# CD6871X3_7_3.net
KiCad netlist of a schematic drawn in EAGLE
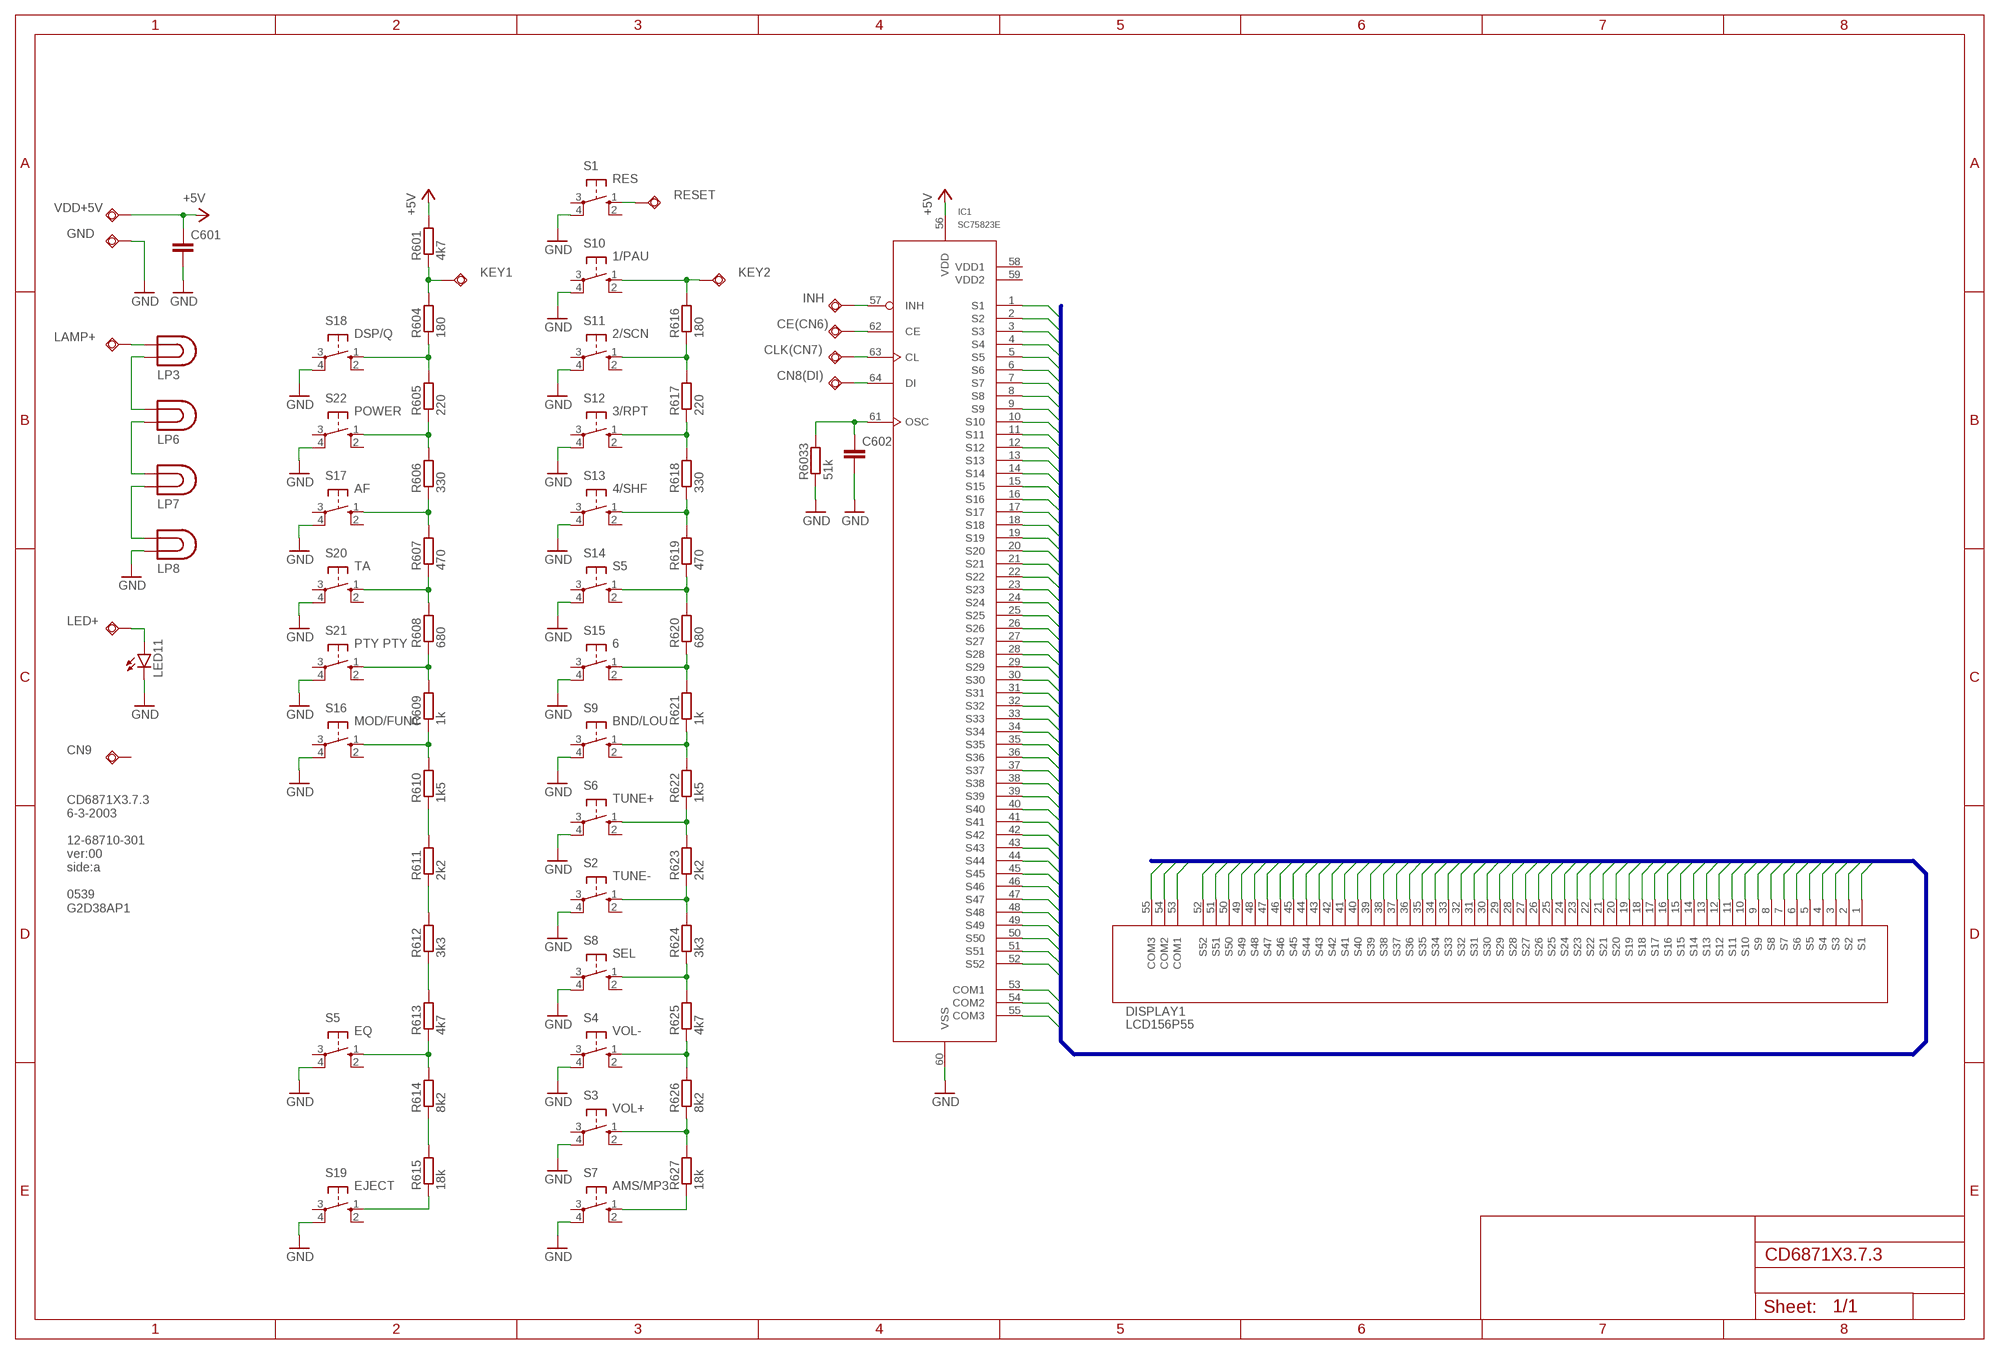
[diagram p0: schematic, sheet 1]

(export (version "E")
  (design (tool "Eeschema 10.0.6"))
  (components
    (comp (ref "C601")
      (value "C-EUC1310")
      (footprint "eagle-import:C1310")
      (libsource (lib "eagle-import") (part "C-EUC1310"))
    )
    (comp (ref "C602")
      (value "C-EUC1310")
      (footprint "eagle-import:C1310")
      (libsource (lib "eagle-import") (part "C-EUC1310"))
    )
    (comp (ref "CE(CN6)")
      (value "TPSQTP20SQ")
      (footprint "eagle-import:TP20SQ")
      (libsource (lib "eagle-import") (part "TPSQTP20SQ"))
    )
    (comp (ref "CLK(CN7)")
      (value "TPSQTP20SQ")
      (footprint "eagle-import:TP20SQ")
      (libsource (lib "eagle-import") (part "TPSQTP20SQ"))
    )
    (comp (ref "CN8(DI)")
      (value "TPSQTP20SQ")
      (footprint "eagle-import:TP20SQ")
      (libsource (lib "eagle-import") (part "TPSQTP20SQ"))
    )
    (comp (ref "CN9")
      (value "TPSQTP20SQ")
      (footprint "eagle-import:TP20SQ")
      (libsource (lib "eagle-import") (part "TPSQTP20SQ"))
    )
    (comp (ref "DISPLAY1")
      (value "LCD156P55")
      (footprint "eagle-import:LCD156P55")
      (libsource (lib "eagle-import") (part "LCD156P55"))
    )
    (comp (ref "GND")
      (value "TPSQTP20SQ")
      (footprint "eagle-import:TP20SQ")
      (libsource (lib "eagle-import") (part "TPSQTP20SQ"))
    )
    (comp (ref "IC1")
      (value "SC75823E")
      (footprint "eagle-import:QFP64_SOT393")
      (libsource (lib "eagle-import") (part "SC75823E"))
    )
    (comp (ref "INH")
      (value "TPSQTP20SQ")
      (footprint "eagle-import:TP20SQ")
      (libsource (lib "eagle-import") (part "TPSQTP20SQ"))
    )
    (comp (ref "KEY1")
      (value "TPSQTP20SQ")
      (footprint "eagle-import:TP20SQ")
      (libsource (lib "eagle-import") (part "TPSQTP20SQ"))
    )
    (comp (ref "KEY2")
      (value "TPSQTP20SQ")
      (footprint "eagle-import:TP20SQ")
      (libsource (lib "eagle-import") (part "TPSQTP20SQ"))
    )
    (comp (ref "LAMP+")
      (value "TPSQTP20SQ")
      (footprint "eagle-import:TP20SQ")
      (libsource (lib "eagle-import") (part "TPSQTP20SQ"))
    )
    (comp (ref "LED+")
      (value "TPSQTP20SQ")
      (footprint "eagle-import:TP20SQ")
      (libsource (lib "eagle-import") (part "TPSQTP20SQ"))
    )
    (comp (ref "LED11")
      (value "LED3MM")
      (footprint "eagle-import:LED3MM")
      (libsource (lib "eagle-import") (part "LED3MM"))
    )
    (comp (ref "LP3")
      (value "LAMP")
      (footprint "eagle-import:LDH-5R")
      (libsource (lib "eagle-import") (part "LAMP"))
    )
    (comp (ref "LP6")
      (value "LAMP")
      (footprint "eagle-import:LDH-5R")
      (libsource (lib "eagle-import") (part "LAMP"))
    )
    (comp (ref "LP7")
      (value "LAMP")
      (footprint "eagle-import:LDH-5R")
      (libsource (lib "eagle-import") (part "LAMP"))
    )
    (comp (ref "LP8")
      (value "LAMP")
      (footprint "eagle-import:LDH-5R")
      (libsource (lib "eagle-import") (part "LAMP"))
    )
    (comp (ref "R601")
      (value "4k7")
      (footprint "eagle-import:M1406")
      (libsource (lib "eagle-import") (part "R-EU_M1406"))
    )
    (comp (ref "R604")
      (value "180")
      (footprint "eagle-import:M1406")
      (libsource (lib "eagle-import") (part "R-EU_M1406"))
    )
    (comp (ref "R605")
      (value "220")
      (footprint "eagle-import:M1406")
      (libsource (lib "eagle-import") (part "R-EU_M1406"))
    )
    (comp (ref "R606")
      (value "330")
      (footprint "eagle-import:M1406")
      (libsource (lib "eagle-import") (part "R-EU_M1406"))
    )
    (comp (ref "R607")
      (value "470")
      (footprint "eagle-import:M1406")
      (libsource (lib "eagle-import") (part "R-EU_M1406"))
    )
    (comp (ref "R608")
      (value "680")
      (footprint "eagle-import:M1406")
      (libsource (lib "eagle-import") (part "R-EU_M1406"))
    )
    (comp (ref "R609")
      (value "1k")
      (footprint "eagle-import:M1406")
      (libsource (lib "eagle-import") (part "R-EU_M1406"))
    )
    (comp (ref "R610")
      (value "1k5")
      (footprint "eagle-import:M1406")
      (libsource (lib "eagle-import") (part "R-EU_M1406"))
    )
    (comp (ref "R611")
      (value "2k2")
      (footprint "eagle-import:M1406")
      (libsource (lib "eagle-import") (part "R-EU_M1406"))
    )
    (comp (ref "R612")
      (value "3k3")
      (footprint "eagle-import:M1406")
      (libsource (lib "eagle-import") (part "R-EU_M1406"))
    )
    (comp (ref "R613")
      (value "4k7")
      (footprint "eagle-import:M1406")
      (libsource (lib "eagle-import") (part "R-EU_M1406"))
    )
    (comp (ref "R614")
      (value "8k2")
      (footprint "eagle-import:M1406")
      (libsource (lib "eagle-import") (part "R-EU_M1406"))
    )
    (comp (ref "R615")
      (value "18k")
      (footprint "eagle-import:M1406")
      (libsource (lib "eagle-import") (part "R-EU_M1406"))
    )
    (comp (ref "R616")
      (value "180")
      (footprint "eagle-import:M1406")
      (libsource (lib "eagle-import") (part "R-EU_M1406"))
    )
    (comp (ref "R617")
      (value "220")
      (footprint "eagle-import:M1406")
      (libsource (lib "eagle-import") (part "R-EU_M1406"))
    )
    (comp (ref "R618")
      (value "330")
      (footprint "eagle-import:M1406")
      (libsource (lib "eagle-import") (part "R-EU_M1406"))
    )
    (comp (ref "R619")
      (value "470")
      (footprint "eagle-import:M1406")
      (libsource (lib "eagle-import") (part "R-EU_M1406"))
    )
    (comp (ref "R620")
      (value "680")
      (footprint "eagle-import:M1406")
      (libsource (lib "eagle-import") (part "R-EU_M1406"))
    )
    (comp (ref "R621")
      (value "1k")
      (footprint "eagle-import:M1406")
      (libsource (lib "eagle-import") (part "R-EU_M1406"))
    )
    (comp (ref "R622")
      (value "1k5")
      (footprint "eagle-import:M1406")
      (libsource (lib "eagle-import") (part "R-EU_M1406"))
    )
    (comp (ref "R623")
      (value "2k2")
      (footprint "eagle-import:M1406")
      (libsource (lib "eagle-import") (part "R-EU_M1406"))
    )
    (comp (ref "R624")
      (value "3k3")
      (footprint "eagle-import:M1406")
      (libsource (lib "eagle-import") (part "R-EU_M1406"))
    )
    (comp (ref "R625")
      (value "4k7")
      (footprint "eagle-import:M1406")
      (libsource (lib "eagle-import") (part "R-EU_M1406"))
    )
    (comp (ref "R626")
      (value "8k2")
      (footprint "eagle-import:M1406")
      (libsource (lib "eagle-import") (part "R-EU_M1406"))
    )
    (comp (ref "R627")
      (value "18k")
      (footprint "eagle-import:M1406")
      (libsource (lib "eagle-import") (part "R-EU_M1406"))
    )
    (comp (ref "R6033")
      (value "51k")
      (footprint "eagle-import:M1406")
      (libsource (lib "eagle-import") (part "R-EU_M1406"))
    )
    (comp (ref "RESET")
      (value "TPSQTP20SQ")
      (footprint "eagle-import:TP20SQ")
      (libsource (lib "eagle-import") (part "TPSQTP20SQ"))
    )
    (comp (ref "S1")
      (value "RES")
      (footprint "eagle-import:B3F-10XX")
      (fields (field (name "MPN") "B3F-1000"))
      (libsource (lib "eagle-import") (part "10-XX"))
    )
    (comp (ref "S2")
      (value "TUNE-")
      (footprint "eagle-import:B3F-10XX")
      (fields (field (name "MPN") "B3F-1000"))
      (libsource (lib "eagle-import") (part "10-XX"))
    )
    (comp (ref "S3")
      (value "VOL+")
      (footprint "eagle-import:B3F-10XX")
      (fields (field (name "MPN") "B3F-1000"))
      (libsource (lib "eagle-import") (part "10-XX"))
    )
    (comp (ref "S4")
      (value "VOL-")
      (footprint "eagle-import:B3F-10XX")
      (fields (field (name "MPN") "B3F-1000"))
      (libsource (lib "eagle-import") (part "10-XX"))
    )
    (comp (ref "S5")
      (value "EQ")
      (footprint "eagle-import:B3F-10XX")
      (fields (field (name "MPN") "B3F-1000"))
      (libsource (lib "eagle-import") (part "10-XX"))
    )
    (comp (ref "S6")
      (value "TUNE+")
      (footprint "eagle-import:B3F-10XX")
      (fields (field (name "MPN") "B3F-1000"))
      (libsource (lib "eagle-import") (part "10-XX"))
    )
    (comp (ref "S7")
      (value "AMS/MP3")
      (footprint "eagle-import:B3F-10XX")
      (fields (field (name "MPN") "B3F-1000"))
      (libsource (lib "eagle-import") (part "10-XX"))
    )
    (comp (ref "S8")
      (value "SEL")
      (footprint "eagle-import:B3F-10XX")
      (fields (field (name "MPN") "B3F-1000"))
      (libsource (lib "eagle-import") (part "10-XX"))
    )
    (comp (ref "S9")
      (value "BND/LOU")
      (footprint "eagle-import:B3F-10XX")
      (fields (field (name "MPN") "B3F-1000"))
      (libsource (lib "eagle-import") (part "10-XX"))
    )
    (comp (ref "S10")
      (value "1/PAU")
      (footprint "eagle-import:B3F-10XX")
      (fields (field (name "MPN") "B3F-1000"))
      (libsource (lib "eagle-import") (part "10-XX"))
    )
    (comp (ref "S11")
      (value "2/SCN")
      (footprint "eagle-import:B3F-10XX")
      (fields (field (name "MPN") "B3F-1000"))
      (libsource (lib "eagle-import") (part "10-XX"))
    )
    (comp (ref "S12")
      (value "3/RPT")
      (footprint "eagle-import:B3F-10XX")
      (fields (field (name "MPN") "B3F-1000"))
      (libsource (lib "eagle-import") (part "10-XX"))
    )
    (comp (ref "S13")
      (value "4/SHF")
      (footprint "eagle-import:B3F-10XX")
      (fields (field (name "MPN") "B3F-1000"))
      (libsource (lib "eagle-import") (part "10-XX"))
    )
    (comp (ref "S14")
      (value "S5")
      (footprint "eagle-import:B3F-10XX")
      (fields (field (name "MPN") "B3F-1000"))
      (libsource (lib "eagle-import") (part "10-XX"))
    )
    (comp (ref "S15")
      (value "6")
      (footprint "eagle-import:B3F-10XX")
      (fields (field (name "MPN") "B3F-1000"))
      (libsource (lib "eagle-import") (part "10-XX"))
    )
    (comp (ref "S16")
      (value "MOD/FUNC")
      (footprint "eagle-import:B3F-10XX")
      (fields (field (name "MPN") "B3F-1000"))
      (libsource (lib "eagle-import") (part "10-XX"))
    )
    (comp (ref "S17")
      (value "AF")
      (footprint "eagle-import:B3F-10XX")
      (fields (field (name "MPN") "B3F-1000"))
      (libsource (lib "eagle-import") (part "10-XX"))
    )
    (comp (ref "S18")
      (value "DSP/Q")
      (footprint "eagle-import:B3F-10XX")
      (fields (field (name "MPN") "B3F-1000"))
      (libsource (lib "eagle-import") (part "10-XX"))
    )
    (comp (ref "S19")
      (value "EJECT")
      (footprint "eagle-import:B3F-10XX")
      (fields (field (name "MPN") "B3F-1000"))
      (libsource (lib "eagle-import") (part "10-XX"))
    )
    (comp (ref "S20")
      (value "TA")
      (footprint "eagle-import:B3F-10XX")
      (fields (field (name "MPN") "B3F-1000"))
      (libsource (lib "eagle-import") (part "10-XX"))
    )
    (comp (ref "S21")
      (value "PTY PTY")
      (footprint "eagle-import:B3F-10XX")
      (fields (field (name "MPN") "B3F-1000"))
      (libsource (lib "eagle-import") (part "10-XX"))
    )
    (comp (ref "S22")
      (value "POWER")
      (footprint "eagle-import:B3F-10XX")
      (fields (field (name "MPN") "B3F-1000"))
      (libsource (lib "eagle-import") (part "10-XX"))
    )
    (comp (ref "VDD+5V")
      (value "TPSQTP20SQ")
      (footprint "eagle-import:TP20SQ")
      (libsource (lib "eagle-import") (part "TPSQTP20SQ"))
    )
  )
  (nets
    (net (code "1") (name "+5V") (class "Default")
      (node (ref "C601") (pin "1") (pinfunction "1_1") (pintype "passive"))
      (node (ref "IC1") (pin "56") (pinfunction "VDD_56") (pintype "power_in"))
      (node (ref "R601") (pin "2") (pinfunction "2_2") (pintype "passive"))
      (node (ref "VDD+5V") (pin "TP") (pinfunction "TP_TP") (pintype "input"))
    )
    (net (code "2") (name "/B$1") (class "Default")
      (node (ref "DISPLAY1") (pin "1") (pinfunction "S1_1") (pintype "input"))
      (node (ref "IC1") (pin "1") (pinfunction "S1_1") (pintype "output"))
    )
    (net (code "3") (name "/B$2") (class "Default")
      (node (ref "DISPLAY1") (pin "2") (pinfunction "S2_2") (pintype "input"))
      (node (ref "IC1") (pin "2") (pinfunction "S2_2") (pintype "output"))
    )
    (net (code "4") (name "/B$3") (class "Default")
      (node (ref "DISPLAY1") (pin "3") (pinfunction "S3_3") (pintype "input"))
      (node (ref "IC1") (pin "3") (pinfunction "S3_3") (pintype "output"))
    )
    (net (code "5") (name "/B$4") (class "Default")
      (node (ref "DISPLAY1") (pin "4") (pinfunction "S4_4") (pintype "input"))
      (node (ref "IC1") (pin "4") (pinfunction "S4_4") (pintype "output"))
    )
    (net (code "6") (name "/B$5") (class "Default")
      (node (ref "DISPLAY1") (pin "5") (pinfunction "S5_5") (pintype "input"))
      (node (ref "IC1") (pin "5") (pinfunction "S5_5") (pintype "output"))
    )
    (net (code "7") (name "/B$6") (class "Default")
      (node (ref "DISPLAY1") (pin "6") (pinfunction "S6_6") (pintype "input"))
      (node (ref "IC1") (pin "6") (pinfunction "S6_6") (pintype "output"))
    )
    (net (code "8") (name "/B$7") (class "Default")
      (node (ref "DISPLAY1") (pin "7") (pinfunction "S7_7") (pintype "input"))
      (node (ref "IC1") (pin "7") (pinfunction "S7_7") (pintype "output"))
    )
    (net (code "9") (name "/B$8") (class "Default")
      (node (ref "DISPLAY1") (pin "8") (pinfunction "S8_8") (pintype "input"))
      (node (ref "IC1") (pin "8") (pinfunction "S8_8") (pintype "output"))
    )
    (net (code "10") (name "/B$9") (class "Default")
      (node (ref "DISPLAY1") (pin "9") (pinfunction "S9_9") (pintype "input"))
      (node (ref "IC1") (pin "9") (pinfunction "S9_9") (pintype "output"))
    )
    (net (code "11") (name "/B$10") (class "Default")
      (node (ref "DISPLAY1") (pin "10") (pinfunction "S10_10") (pintype "input"))
      (node (ref "IC1") (pin "10") (pinfunction "S10_10") (pintype "output"))
    )
    (net (code "12") (name "/B$11") (class "Default")
      (node (ref "DISPLAY1") (pin "11") (pinfunction "S11_11") (pintype "input"))
      (node (ref "IC1") (pin "11") (pinfunction "S11_11") (pintype "output"))
    )
    (net (code "13") (name "/B$12") (class "Default")
      (node (ref "DISPLAY1") (pin "12") (pinfunction "S12_12") (pintype "input"))
      (node (ref "IC1") (pin "12") (pinfunction "S12_12") (pintype "output"))
    )
    (net (code "14") (name "/B$13") (class "Default")
      (node (ref "DISPLAY1") (pin "13") (pinfunction "S13_13") (pintype "input"))
      (node (ref "IC1") (pin "13") (pinfunction "S13_13") (pintype "output"))
    )
    (net (code "15") (name "/B$14") (class "Default")
      (node (ref "DISPLAY1") (pin "14") (pinfunction "S14_14") (pintype "input"))
      (node (ref "IC1") (pin "14") (pinfunction "S14_14") (pintype "output"))
    )
    (net (code "16") (name "/B$15") (class "Default")
      (node (ref "DISPLAY1") (pin "15") (pinfunction "S15_15") (pintype "input"))
      (node (ref "IC1") (pin "15") (pinfunction "S15_15") (pintype "output"))
    )
    (net (code "17") (name "/B$16") (class "Default")
      (node (ref "DISPLAY1") (pin "16") (pinfunction "S16_16") (pintype "input"))
      (node (ref "IC1") (pin "16") (pinfunction "S16_16") (pintype "output"))
    )
    (net (code "18") (name "/B$17") (class "Default")
      (node (ref "DISPLAY1") (pin "17") (pinfunction "S17_17") (pintype "input"))
      (node (ref "IC1") (pin "17") (pinfunction "S17_17") (pintype "output"))
    )
    (net (code "19") (name "/B$18") (class "Default")
      (node (ref "DISPLAY1") (pin "18") (pinfunction "S18_18") (pintype "input"))
      (node (ref "IC1") (pin "18") (pinfunction "S18_18") (pintype "output"))
    )
    (net (code "20") (name "/B$19") (class "Default")
      (node (ref "DISPLAY1") (pin "19") (pinfunction "S19_19") (pintype "input"))
      (node (ref "IC1") (pin "19") (pinfunction "S19_19") (pintype "output"))
    )
    (net (code "21") (name "/B$20") (class "Default")
      (node (ref "DISPLAY1") (pin "20") (pinfunction "S20_20") (pintype "input"))
      (node (ref "IC1") (pin "20") (pinfunction "S20_20") (pintype "output"))
    )
    (net (code "22") (name "/B$21") (class "Default")
      (node (ref "DISPLAY1") (pin "21") (pinfunction "S21_21") (pintype "input"))
      (node (ref "IC1") (pin "21") (pinfunction "S21_21") (pintype "output"))
    )
    (net (code "23") (name "/B$22") (class "Default")
      (node (ref "DISPLAY1") (pin "22") (pinfunction "S22_22") (pintype "input"))
      (node (ref "IC1") (pin "22") (pinfunction "S22_22") (pintype "output"))
    )
    (net (code "24") (name "/B$23") (class "Default")
      (node (ref "DISPLAY1") (pin "23") (pinfunction "S23_23") (pintype "input"))
      (node (ref "IC1") (pin "23") (pinfunction "S23_23") (pintype "output"))
    )
    (net (code "25") (name "/B$24") (class "Default")
      (node (ref "DISPLAY1") (pin "24") (pinfunction "S24_24") (pintype "input"))
      (node (ref "IC1") (pin "24") (pinfunction "S24_24") (pintype "output"))
    )
    (net (code "26") (name "/B$25") (class "Default")
      (node (ref "DISPLAY1") (pin "25") (pinfunction "S25_25") (pintype "input"))
      (node (ref "IC1") (pin "25") (pinfunction "S25_25") (pintype "output"))
    )
    (net (code "27") (name "/B$26") (class "Default")
      (node (ref "DISPLAY1") (pin "26") (pinfunction "S26_26") (pintype "input"))
      (node (ref "IC1") (pin "26") (pinfunction "S26_26") (pintype "output"))
    )
    (net (code "28") (name "/B$27") (class "Default")
      (node (ref "DISPLAY1") (pin "27") (pinfunction "S27_27") (pintype "input"))
      (node (ref "IC1") (pin "27") (pinfunction "S27_27") (pintype "output"))
    )
    (net (code "29") (name "/B$28") (class "Default")
      (node (ref "DISPLAY1") (pin "28") (pinfunction "S28_28") (pintype "input"))
      (node (ref "IC1") (pin "28") (pinfunction "S28_28") (pintype "output"))
    )
    (net (code "30") (name "/B$29") (class "Default")
      (node (ref "DISPLAY1") (pin "29") (pinfunction "S29_29") (pintype "input"))
      (node (ref "IC1") (pin "29") (pinfunction "S29_29") (pintype "output"))
    )
    (net (code "31") (name "/B$30") (class "Default")
      (node (ref "DISPLAY1") (pin "30") (pinfunction "S30_30") (pintype "input"))
      (node (ref "IC1") (pin "30") (pinfunction "S30_30") (pintype "output"))
    )
    (net (code "32") (name "/B$31") (class "Default")
      (node (ref "DISPLAY1") (pin "31") (pinfunction "S31_31") (pintype "input"))
      (node (ref "IC1") (pin "31") (pinfunction "S31_31") (pintype "output"))
    )
    (net (code "33") (name "/B$32") (class "Default")
      (node (ref "DISPLAY1") (pin "32") (pinfunction "S32_32") (pintype "input"))
      (node (ref "IC1") (pin "32") (pinfunction "S32_32") (pintype "output"))
    )
    (net (code "34") (name "/B$33") (class "Default")
      (node (ref "DISPLAY1") (pin "33") (pinfunction "S33_33") (pintype "input"))
      (node (ref "IC1") (pin "33") (pinfunction "S33_33") (pintype "output"))
    )
    (net (code "35") (name "/B$34") (class "Default")
      (node (ref "DISPLAY1") (pin "34") (pinfunction "S34_34") (pintype "input"))
      (node (ref "IC1") (pin "34") (pinfunction "S34_34") (pintype "output"))
    )
    (net (code "36") (name "/B$35") (class "Default")
      (node (ref "DISPLAY1") (pin "35") (pinfunction "S35_35") (pintype "input"))
      (node (ref "IC1") (pin "35") (pinfunction "S35_35") (pintype "output"))
    )
    (net (code "37") (name "/B$36") (class "Default")
      (node (ref "DISPLAY1") (pin "36") (pinfunction "S36_36") (pintype "input"))
      (node (ref "IC1") (pin "36") (pinfunction "S36_36") (pintype "output"))
    )
    (net (code "38") (name "/B$37") (class "Default")
      (node (ref "DISPLAY1") (pin "37") (pinfunction "S37_37") (pintype "input"))
      (node (ref "IC1") (pin "37") (pinfunction "S37_37") (pintype "output"))
    )
    (net (code "39") (name "/B$38") (class "Default")
      (node (ref "DISPLAY1") (pin "38") (pinfunction "S38_38") (pintype "input"))
      (node (ref "IC1") (pin "38") (pinfunction "S38_38") (pintype "output"))
    )
    (net (code "40") (name "/B$39") (class "Default")
      (node (ref "DISPLAY1") (pin "39") (pinfunction "S39_39") (pintype "input"))
      (node (ref "IC1") (pin "39") (pinfunction "S39_39") (pintype "output"))
    )
    (net (code "41") (name "/B$40") (class "Default")
      (node (ref "DISPLAY1") (pin "40") (pinfunction "S40_40") (pintype "input"))
      (node (ref "IC1") (pin "40") (pinfunction "S40_40") (pintype "output"))
    )
    (net (code "42") (name "/B$41") (class "Default")
      (node (ref "DISPLAY1") (pin "41") (pinfunction "S41_41") (pintype "input"))
      (node (ref "IC1") (pin "41") (pinfunction "S41_41") (pintype "output"))
    )
    (net (code "43") (name "/B$42") (class "Default")
      (node (ref "DISPLAY1") (pin "42") (pinfunction "S42_42") (pintype "input"))
      (node (ref "IC1") (pin "42") (pinfunction "S42_42") (pintype "output"))
    )
    (net (code "44") (name "/B$43") (class "Default")
      (node (ref "DISPLAY1") (pin "43") (pinfunction "S43_43") (pintype "input"))
      (node (ref "IC1") (pin "43") (pinfunction "S43_43") (pintype "output"))
    )
    (net (code "45") (name "/B$44") (class "Default")
      (node (ref "DISPLAY1") (pin "44") (pinfunction "S44_44") (pintype "input"))
      (node (ref "IC1") (pin "44") (pinfunction "S44_44") (pintype "output"))
    )
    (net (code "46") (name "/B$45") (class "Default")
      (node (ref "DISPLAY1") (pin "45") (pinfunction "S45_45") (pintype "input"))
      (node (ref "IC1") (pin "45") (pinfunction "S45_45") (pintype "output"))
    )
    (net (code "47") (name "/B$46") (class "Default")
      (node (ref "DISPLAY1") (pin "46") (pinfunction "S46_46") (pintype "input"))
      (node (ref "IC1") (pin "46") (pinfunction "S46_46") (pintype "output"))
    )
    (net (code "48") (name "/B$47") (class "Default")
      (node (ref "DISPLAY1") (pin "47") (pinfunction "S47_47") (pintype "input"))
      (node (ref "IC1") (pin "47") (pinfunction "S47_47") (pintype "output"))
    )
    (net (code "49") (name "/B$48") (class "Default")
      (node (ref "DISPLAY1") (pin "48") (pinfunction "S48_48") (pintype "input"))
      (node (ref "IC1") (pin "48") (pinfunction "S48_48") (pintype "output"))
    )
    (net (code "50") (name "/B$49") (class "Default")
      (node (ref "DISPLAY1") (pin "49") (pinfunction "S49_49") (pintype "input"))
      (node (ref "IC1") (pin "49") (pinfunction "S49_49") (pintype "output"))
    )
    (net (code "51") (name "/B$50") (class "Default")
      (node (ref "DISPLAY1") (pin "50") (pinfunction "S50_50") (pintype "input"))
      (node (ref "IC1") (pin "50") (pinfunction "S50_50") (pintype "output"))
    )
    (net (code "52") (name "/B$51") (class "Default")
      (node (ref "DISPLAY1") (pin "51") (pinfunction "S51_51") (pintype "input"))
      (node (ref "IC1") (pin "51") (pinfunction "S51_51") (pintype "output"))
    )
    (net (code "53") (name "/B$52") (class "Default")
      (node (ref "DISPLAY1") (pin "52") (pinfunction "S52_52") (pintype "input"))
      (node (ref "IC1") (pin "52") (pinfunction "S52_52") (pintype "output"))
    )
    (net (code "54") (name "/B$53") (class "Default")
      (node (ref "DISPLAY1") (pin "53") (pinfunction "COM1_53") (pintype "input"))
      (node (ref "IC1") (pin "53") (pinfunction "COM1_53") (pintype "output"))
    )
    (net (code "55") (name "/B$54") (class "Default")
      (node (ref "DISPLAY1") (pin "54") (pinfunction "COM2_54") (pintype "input"))
      (node (ref "IC1") (pin "54") (pinfunction "COM2_54") (pintype "output"))
    )
    (net (code "56") (name "/B$55") (class "Default")
      (node (ref "DISPLAY1") (pin "55") (pinfunction "COM3_55") (pintype "input"))
      (node (ref "IC1") (pin "55") (pinfunction "COM3_55") (pintype "output"))
    )
    (net (code "57") (name "GND") (class "Default")
      (node (ref "C601") (pin "2") (pinfunction "2_2") (pintype "passive"))
      (node (ref "C602") (pin "2") (pinfunction "2_2") (pintype "passive"))
      (node (ref "GND") (pin "TP") (pinfunction "TP_TP") (pintype "input"))
      (node (ref "IC1") (pin "60") (pinfunction "VSS_60") (pintype "power_in"))
      (node (ref "LED11") (pin "K") (pinfunction "C_K") (pintype "passive"))
      (node (ref "LP8") (pin "1") (pinfunction "1_1") (pintype "passive"))
      (node (ref "R6033") (pin "1") (pinfunction "1_1") (pintype "passive"))
      (node (ref "S1") (pin "4") (pinfunction "P1_4") (pintype "passive"))
      (node (ref "S10") (pin "4") (pinfunction "P1_4") (pintype "passive"))
      (node (ref "S11") (pin "4") (pinfunction "P1_4") (pintype "passive"))
      (node (ref "S12") (pin "4") (pinfunction "P1_4") (pintype "passive"))
      (node (ref "S13") (pin "4") (pinfunction "P1_4") (pintype "passive"))
      (node (ref "S14") (pin "4") (pinfunction "P1_4") (pintype "passive"))
      (node (ref "S15") (pin "4") (pinfunction "P1_4") (pintype "passive"))
      (node (ref "S16") (pin "4") (pinfunction "P1_4") (pintype "passive"))
      (node (ref "S17") (pin "4") (pinfunction "P1_4") (pintype "passive"))
      (node (ref "S18") (pin "4") (pinfunction "P1_4") (pintype "passive"))
      (node (ref "S19") (pin "4") (pinfunction "P1_4") (pintype "passive"))
      (node (ref "S2") (pin "4") (pinfunction "P1_4") (pintype "passive"))
      (node (ref "S20") (pin "4") (pinfunction "P1_4") (pintype "passive"))
      (node (ref "S21") (pin "4") (pinfunction "P1_4") (pintype "passive"))
      (node (ref "S22") (pin "4") (pinfunction "P1_4") (pintype "passive"))
      (node (ref "S3") (pin "4") (pinfunction "P1_4") (pintype "passive"))
      (node (ref "S4") (pin "4") (pinfunction "P1_4") (pintype "passive"))
      (node (ref "S5") (pin "4") (pinfunction "P1_4") (pintype "passive"))
      (node (ref "S6") (pin "4") (pinfunction "P1_4") (pintype "passive"))
      (node (ref "S7") (pin "4") (pinfunction "P1_4") (pintype "passive"))
      (node (ref "S8") (pin "4") (pinfunction "P1_4") (pintype "passive"))
      (node (ref "S9") (pin "4") (pinfunction "P1_4") (pintype "passive"))
    )
    (net (code "58") (name "Net-(IC1-CE)") (class "Default")
      (node (ref "CE(CN6)") (pin "TP") (pinfunction "TP_TP") (pintype "input"))
      (node (ref "IC1") (pin "62") (pinfunction "CE_62") (pintype "input"))
    )
    (net (code "59") (name "Net-(IC1-CL)") (class "Default")
      (node (ref "CLK(CN7)") (pin "TP") (pinfunction "TP_TP") (pintype "input"))
      (node (ref "IC1") (pin "63") (pinfunction "CL_63") (pintype "input"))
    )
    (net (code "60") (name "Net-(IC1-DI)") (class "Default")
      (node (ref "CN8(DI)") (pin "TP") (pinfunction "TP_TP") (pintype "input"))
      (node (ref "IC1") (pin "64") (pinfunction "DI_64") (pintype "input"))
    )
    (net (code "61") (name "Net-(IC1-INH)") (class "Default")
      (node (ref "IC1") (pin "57") (pinfunction "INH_57") (pintype "input"))
      (node (ref "INH") (pin "TP") (pinfunction "TP_TP") (pintype "input"))
    )
    (net (code "62") (name "Net-(IC1-OSC)") (class "Default")
      (node (ref "C602") (pin "1") (pinfunction "1_1") (pintype "passive"))
      (node (ref "IC1") (pin "61") (pinfunction "OSC_61") (pintype "input"))
      (node (ref "R6033") (pin "2") (pinfunction "2_2") (pintype "passive"))
    )
    (net (code "63") (name "Net-(KEY1-PadTP)") (class "Default")
      (node (ref "KEY1") (pin "TP") (pinfunction "TP_TP") (pintype "input"))
      (node (ref "R601") (pin "1") (pinfunction "1_1") (pintype "passive"))
      (node (ref "R604") (pin "2") (pinfunction "2_2") (pintype "passive"))
    )
    (net (code "64") (name "Net-(LAMP+-PadTP)") (class "Default")
      (node (ref "LAMP+") (pin "TP") (pinfunction "TP_TP") (pintype "input"))
      (node (ref "LP3") (pin "2") (pinfunction "2_2") (pintype "passive"))
    )
    (net (code "65") (name "Net-(LED+-PadTP)") (class "Default")
      (node (ref "LED+") (pin "TP") (pinfunction "TP_TP") (pintype "input"))
      (node (ref "LED11") (pin "A") (pinfunction "A_A") (pintype "passive"))
    )
    (net (code "66") (name "Net-(LP3-Pad1)") (class "Default")
      (node (ref "LP3") (pin "1") (pinfunction "1_1") (pintype "passive"))
      (node (ref "LP6") (pin "2") (pinfunction "2_2") (pintype "passive"))
    )
    (net (code "67") (name "Net-(LP6-Pad1)") (class "Default")
      (node (ref "LP6") (pin "1") (pinfunction "1_1") (pintype "passive"))
      (node (ref "LP7") (pin "2") (pinfunction "2_2") (pintype "passive"))
    )
    (net (code "68") (name "Net-(LP7-Pad1)") (class "Default")
      (node (ref "LP7") (pin "1") (pinfunction "1_1") (pintype "passive"))
      (node (ref "LP8") (pin "2") (pinfunction "2_2") (pintype "passive"))
    )
    (net (code "69") (name "Net-(R610-Pad1)") (class "Default")
      (node (ref "R610") (pin "1") (pinfunction "1_1") (pintype "passive"))
      (node (ref "R611") (pin "2") (pinfunction "2_2") (pintype "passive"))
    )
    (net (code "70") (name "Net-(R611-Pad1)") (class "Default")
      (node (ref "R611") (pin "1") (pinfunction "1_1") (pintype "passive"))
      (node (ref "R612") (pin "2") (pinfunction "2_2") (pintype "passive"))
    )
    (net (code "71") (name "Net-(R612-Pad1)") (class "Default")
      (node (ref "R612") (pin "1") (pinfunction "1_1") (pintype "passive"))
      (node (ref "R613") (pin "2") (pinfunction "2_2") (pintype "passive"))
    )
    (net (code "72") (name "Net-(R614-Pad1)") (class "Default")
      (node (ref "R614") (pin "1") (pinfunction "1_1") (pintype "passive"))
      (node (ref "R615") (pin "2") (pinfunction "2_2") (pintype "passive"))
    )
    (net (code "73") (name "Net-(S1-S)") (class "Default")
      (node (ref "RESET") (pin "TP") (pinfunction "TP_TP") (pintype "input"))
      (node (ref "S1") (pin "1") (pinfunction "S_1") (pintype "passive"))
    )
    (net (code "74") (name "Net-(S2-S)") (class "Default")
      (node (ref "R623") (pin "1") (pinfunction "1_1") (pintype "passive"))
      (node (ref "R624") (pin "2") (pinfunction "2_2") (pintype "passive"))
      (node (ref "S2") (pin "1") (pinfunction "S_1") (pintype "passive"))
    )
    (net (code "75") (name "Net-(S3-S)") (class "Default")
      (node (ref "R626") (pin "1") (pinfunction "1_1") (pintype "passive"))
      (node (ref "R627") (pin "2") (pinfunction "2_2") (pintype "passive"))
      (node (ref "S3") (pin "1") (pinfunction "S_1") (pintype "passive"))
    )
    (net (code "76") (name "Net-(S4-S)") (class "Default")
      (node (ref "R625") (pin "1") (pinfunction "1_1") (pintype "passive"))
      (node (ref "R626") (pin "2") (pinfunction "2_2") (pintype "passive"))
      (node (ref "S4") (pin "1") (pinfunction "S_1") (pintype "passive"))
    )
    (net (code "77") (name "Net-(S5-S)") (class "Default")
      (node (ref "R613") (pin "1") (pinfunction "1_1") (pintype "passive"))
      (node (ref "R614") (pin "2") (pinfunction "2_2") (pintype "passive"))
      (node (ref "S5") (pin "1") (pinfunction "S_1") (pintype "passive"))
    )
    (net (code "78") (name "Net-(S6-S)") (class "Default")
      (node (ref "R622") (pin "1") (pinfunction "1_1") (pintype "passive"))
      (node (ref "R623") (pin "2") (pinfunction "2_2") (pintype "passive"))
      (node (ref "S6") (pin "1") (pinfunction "S_1") (pintype "passive"))
    )
    (net (code "79") (name "Net-(S7-S)") (class "Default")
      (node (ref "R627") (pin "1") (pinfunction "1_1") (pintype "passive"))
      (node (ref "S7") (pin "1") (pinfunction "S_1") (pintype "passive"))
    )
    (net (code "80") (name "Net-(S8-S)") (class "Default")
      (node (ref "R624") (pin "1") (pinfunction "1_1") (pintype "passive"))
      (node (ref "R625") (pin "2") (pinfunction "2_2") (pintype "passive"))
      (node (ref "S8") (pin "1") (pinfunction "S_1") (pintype "passive"))
    )
    (net (code "81") (name "Net-(S9-S)") (class "Default")
      (node (ref "R621") (pin "1") (pinfunction "1_1") (pintype "passive"))
      (node (ref "R622") (pin "2") (pinfunction "2_2") (pintype "passive"))
      (node (ref "S9") (pin "1") (pinfunction "S_1") (pintype "passive"))
    )
    (net (code "82") (name "Net-(S10-S)") (class "Default")
      (node (ref "KEY2") (pin "TP") (pinfunction "TP_TP") (pintype "input"))
      (node (ref "R616") (pin "2") (pinfunction "2_2") (pintype "passive"))
      (node (ref "S10") (pin "1") (pinfunction "S_1") (pintype "passive"))
    )
    (net (code "83") (name "Net-(S11-S)") (class "Default")
      (node (ref "R616") (pin "1") (pinfunction "1_1") (pintype "passive"))
      (node (ref "R617") (pin "2") (pinfunction "2_2") (pintype "passive"))
      (node (ref "S11") (pin "1") (pinfunction "S_1") (pintype "passive"))
    )
    (net (code "84") (name "Net-(S12-S)") (class "Default")
      (node (ref "R617") (pin "1") (pinfunction "1_1") (pintype "passive"))
      (node (ref "R618") (pin "2") (pinfunction "2_2") (pintype "passive"))
      (node (ref "S12") (pin "1") (pinfunction "S_1") (pintype "passive"))
    )
    (net (code "85") (name "Net-(S13-S)") (class "Default")
      (node (ref "R618") (pin "1") (pinfunction "1_1") (pintype "passive"))
      (node (ref "R619") (pin "2") (pinfunction "2_2") (pintype "passive"))
      (node (ref "S13") (pin "1") (pinfunction "S_1") (pintype "passive"))
    )
    (net (code "86") (name "Net-(S14-S)") (class "Default")
      (node (ref "R619") (pin "1") (pinfunction "1_1") (pintype "passive"))
      (node (ref "R620") (pin "2") (pinfunction "2_2") (pintype "passive"))
      (node (ref "S14") (pin "1") (pinfunction "S_1") (pintype "passive"))
    )
    (net (code "87") (name "Net-(S15-S)") (class "Default")
      (node (ref "R620") (pin "1") (pinfunction "1_1") (pintype "passive"))
      (node (ref "R621") (pin "2") (pinfunction "2_2") (pintype "passive"))
      (node (ref "S15") (pin "1") (pinfunction "S_1") (pintype "passive"))
    )
    (net (code "88") (name "Net-(S16-S)") (class "Default")
      (node (ref "R609") (pin "1") (pinfunction "1_1") (pintype "passive"))
      (node (ref "R610") (pin "2") (pinfunction "2_2") (pintype "passive"))
      (node (ref "S16") (pin "1") (pinfunction "S_1") (pintype "passive"))
    )
    (net (code "89") (name "Net-(S17-S)") (class "Default")
      (node (ref "R606") (pin "1") (pinfunction "1_1") (pintype "passive"))
      (node (ref "R607") (pin "2") (pinfunction "2_2") (pintype "passive"))
      (node (ref "S17") (pin "1") (pinfunction "S_1") (pintype "passive"))
    )
    (net (code "90") (name "Net-(S18-S)") (class "Default")
      (node (ref "R604") (pin "1") (pinfunction "1_1") (pintype "passive"))
      (node (ref "R605") (pin "2") (pinfunction "2_2") (pintype "passive"))
      (node (ref "S18") (pin "1") (pinfunction "S_1") (pintype "passive"))
    )
    (net (code "91") (name "Net-(S19-S)") (class "Default")
      (node (ref "R615") (pin "1") (pinfunction "1_1") (pintype "passive"))
      (node (ref "S19") (pin "1") (pinfunction "S_1") (pintype "passive"))
    )
    (net (code "92") (name "Net-(S20-S)") (class "Default")
      (node (ref "R607") (pin "1") (pinfunction "1_1") (pintype "passive"))
      (node (ref "R608") (pin "2") (pinfunction "2_2") (pintype "passive"))
      (node (ref "S20") (pin "1") (pinfunction "S_1") (pintype "passive"))
    )
    (net (code "93") (name "Net-(S21-S)") (class "Default")
      (node (ref "R608") (pin "1") (pinfunction "1_1") (pintype "passive"))
      (node (ref "R609") (pin "2") (pinfunction "2_2") (pintype "passive"))
      (node (ref "S21") (pin "1") (pinfunction "S_1") (pintype "passive"))
    )
    (net (code "94") (name "Net-(S22-S)") (class "Default")
      (node (ref "R605") (pin "1") (pinfunction "1_1") (pintype "passive"))
      (node (ref "R606") (pin "2") (pinfunction "2_2") (pintype "passive"))
      (node (ref "S22") (pin "1") (pinfunction "S_1") (pintype "passive"))
    )
    (net (code "95") (name "unconnected-(CN9-PadTP)") (class "Default")
      (node (ref "CN9") (pin "TP") (pinfunction "TP_TP") (pintype "input"))
    )
    (net (code "96") (name "unconnected-(IC1-VDD1-Pad58)") (class "Default")
      (node (ref "IC1") (pin "58") (pinfunction "VDD1_58") (pintype "output"))
    )
    (net (code "97") (name "unconnected-(IC1-VDD2-Pad59)") (class "Default")
      (node (ref "IC1") (pin "59") (pinfunction "VDD2_59") (pintype "output"))
    )
    (net (code "98") (name "unconnected-(S1-P-Pad3)") (class "Default")
      (node (ref "S1") (pin "3") (pinfunction "P_3") (pintype "passive"))
    )
    (net (code "99") (name "unconnected-(S1-S1-Pad2)") (class "Default")
      (node (ref "S1") (pin "2") (pinfunction "S1_2") (pintype "passive"))
    )
    (net (code "100") (name "unconnected-(S2-P-Pad3)") (class "Default")
      (node (ref "S2") (pin "3") (pinfunction "P_3") (pintype "passive"))
    )
    (net (code "101") (name "unconnected-(S2-S1-Pad2)") (class "Default")
      (node (ref "S2") (pin "2") (pinfunction "S1_2") (pintype "passive"))
    )
    (net (code "102") (name "unconnected-(S3-P-Pad3)") (class "Default")
      (node (ref "S3") (pin "3") (pinfunction "P_3") (pintype "passive"))
    )
    (net (code "103") (name "unconnected-(S3-S1-Pad2)") (class "Default")
      (node (ref "S3") (pin "2") (pinfunction "S1_2") (pintype "passive"))
    )
    (net (code "104") (name "unconnected-(S4-P-Pad3)") (class "Default")
      (node (ref "S4") (pin "3") (pinfunction "P_3") (pintype "passive"))
    )
    (net (code "105") (name "unconnected-(S4-S1-Pad2)") (class "Default")
      (node (ref "S4") (pin "2") (pinfunction "S1_2") (pintype "passive"))
    )
    (net (code "106") (name "unconnected-(S5-P-Pad3)") (class "Default")
      (node (ref "S5") (pin "3") (pinfunction "P_3") (pintype "passive"))
    )
    (net (code "107") (name "unconnected-(S5-S1-Pad2)") (class "Default")
      (node (ref "S5") (pin "2") (pinfunction "S1_2") (pintype "passive"))
    )
    (net (code "108") (name "unconnected-(S6-P-Pad3)") (class "Default")
      (node (ref "S6") (pin "3") (pinfunction "P_3") (pintype "passive"))
    )
    (net (code "109") (name "unconnected-(S6-S1-Pad2)") (class "Default")
      (node (ref "S6") (pin "2") (pinfunction "S1_2") (pintype "passive"))
    )
    (net (code "110") (name "unconnected-(S7-P-Pad3)") (class "Default")
      (node (ref "S7") (pin "3") (pinfunction "P_3") (pintype "passive"))
    )
    (net (code "111") (name "unconnected-(S7-S1-Pad2)") (class "Default")
      (node (ref "S7") (pin "2") (pinfunction "S1_2") (pintype "passive"))
    )
    (net (code "112") (name "unconnected-(S8-P-Pad3)") (class "Default")
      (node (ref "S8") (pin "3") (pinfunction "P_3") (pintype "passive"))
    )
    (net (code "113") (name "unconnected-(S8-S1-Pad2)") (class "Default")
      (node (ref "S8") (pin "2") (pinfunction "S1_2") (pintype "passive"))
    )
    (net (code "114") (name "unconnected-(S9-P-Pad3)") (class "Default")
      (node (ref "S9") (pin "3") (pinfunction "P_3") (pintype "passive"))
    )
    (net (code "115") (name "unconnected-(S9-S1-Pad2)") (class "Default")
      (node (ref "S9") (pin "2") (pinfunction "S1_2") (pintype "passive"))
    )
    (net (code "116") (name "unconnected-(S10-P-Pad3)") (class "Default")
      (node (ref "S10") (pin "3") (pinfunction "P_3") (pintype "passive"))
    )
    (net (code "117") (name "unconnected-(S10-S1-Pad2)") (class "Default")
      (node (ref "S10") (pin "2") (pinfunction "S1_2") (pintype "passive"))
    )
    (net (code "118") (name "unconnected-(S11-P-Pad3)") (class "Default")
      (node (ref "S11") (pin "3") (pinfunction "P_3") (pintype "passive"))
    )
    (net (code "119") (name "unconnected-(S11-S1-Pad2)") (class "Default")
      (node (ref "S11") (pin "2") (pinfunction "S1_2") (pintype "passive"))
    )
    (net (code "120") (name "unconnected-(S12-P-Pad3)") (class "Default")
      (node (ref "S12") (pin "3") (pinfunction "P_3") (pintype "passive"))
    )
    (net (code "121") (name "unconnected-(S12-S1-Pad2)") (class "Default")
      (node (ref "S12") (pin "2") (pinfunction "S1_2") (pintype "passive"))
    )
    (net (code "122") (name "unconnected-(S13-P-Pad3)") (class "Default")
      (node (ref "S13") (pin "3") (pinfunction "P_3") (pintype "passive"))
    )
    (net (code "123") (name "unconnected-(S13-S1-Pad2)") (class "Default")
      (node (ref "S13") (pin "2") (pinfunction "S1_2") (pintype "passive"))
    )
    (net (code "124") (name "unconnected-(S14-P-Pad3)") (class "Default")
      (node (ref "S14") (pin "3") (pinfunction "P_3") (pintype "passive"))
    )
    (net (code "125") (name "unconnected-(S14-S1-Pad2)") (class "Default")
      (node (ref "S14") (pin "2") (pinfunction "S1_2") (pintype "passive"))
    )
    (net (code "126") (name "unconnected-(S15-P-Pad3)") (class "Default")
      (node (ref "S15") (pin "3") (pinfunction "P_3") (pintype "passive"))
    )
    (net (code "127") (name "unconnected-(S15-S1-Pad2)") (class "Default")
      (node (ref "S15") (pin "2") (pinfunction "S1_2") (pintype "passive"))
    )
    (net (code "128") (name "unconnected-(S16-P-Pad3)") (class "Default")
      (node (ref "S16") (pin "3") (pinfunction "P_3") (pintype "passive"))
    )
    (net (code "129") (name "unconnected-(S16-S1-Pad2)") (class "Default")
      (node (ref "S16") (pin "2") (pinfunction "S1_2") (pintype "passive"))
    )
    (net (code "130") (name "unconnected-(S17-P-Pad3)") (class "Default")
      (node (ref "S17") (pin "3") (pinfunction "P_3") (pintype "passive"))
    )
    (net (code "131") (name "unconnected-(S17-S1-Pad2)") (class "Default")
      (node (ref "S17") (pin "2") (pinfunction "S1_2") (pintype "passive"))
    )
    (net (code "132") (name "unconnected-(S18-P-Pad3)") (class "Default")
      (node (ref "S18") (pin "3") (pinfunction "P_3") (pintype "passive"))
    )
    (net (code "133") (name "unconnected-(S18-S1-Pad2)") (class "Default")
      (node (ref "S18") (pin "2") (pinfunction "S1_2") (pintype "passive"))
    )
    (net (code "134") (name "unconnected-(S19-P-Pad3)") (class "Default")
      (node (ref "S19") (pin "3") (pinfunction "P_3") (pintype "passive"))
    )
    (net (code "135") (name "unconnected-(S19-S1-Pad2)") (class "Default")
      (node (ref "S19") (pin "2") (pinfunction "S1_2") (pintype "passive"))
    )
    (net (code "136") (name "unconnected-(S20-P-Pad3)") (class "Default")
      (node (ref "S20") (pin "3") (pinfunction "P_3") (pintype "passive"))
    )
    (net (code "137") (name "unconnected-(S20-S1-Pad2)") (class "Default")
      (node (ref "S20") (pin "2") (pinfunction "S1_2") (pintype "passive"))
    )
    (net (code "138") (name "unconnected-(S21-P-Pad3)") (class "Default")
      (node (ref "S21") (pin "3") (pinfunction "P_3") (pintype "passive"))
    )
    (net (code "139") (name "unconnected-(S21-S1-Pad2)") (class "Default")
      (node (ref "S21") (pin "2") (pinfunction "S1_2") (pintype "passive"))
    )
    (net (code "140") (name "unconnected-(S22-P-Pad3)") (class "Default")
      (node (ref "S22") (pin "3") (pinfunction "P_3") (pintype "passive"))
    )
    (net (code "141") (name "unconnected-(S22-S1-Pad2)") (class "Default")
      (node (ref "S22") (pin "2") (pinfunction "S1_2") (pintype "passive"))
    )
  )
)
